# Adafruit_MEMENTO_Camera_LED_Ring.net
KiCad netlist of a schematic drawn in EAGLE
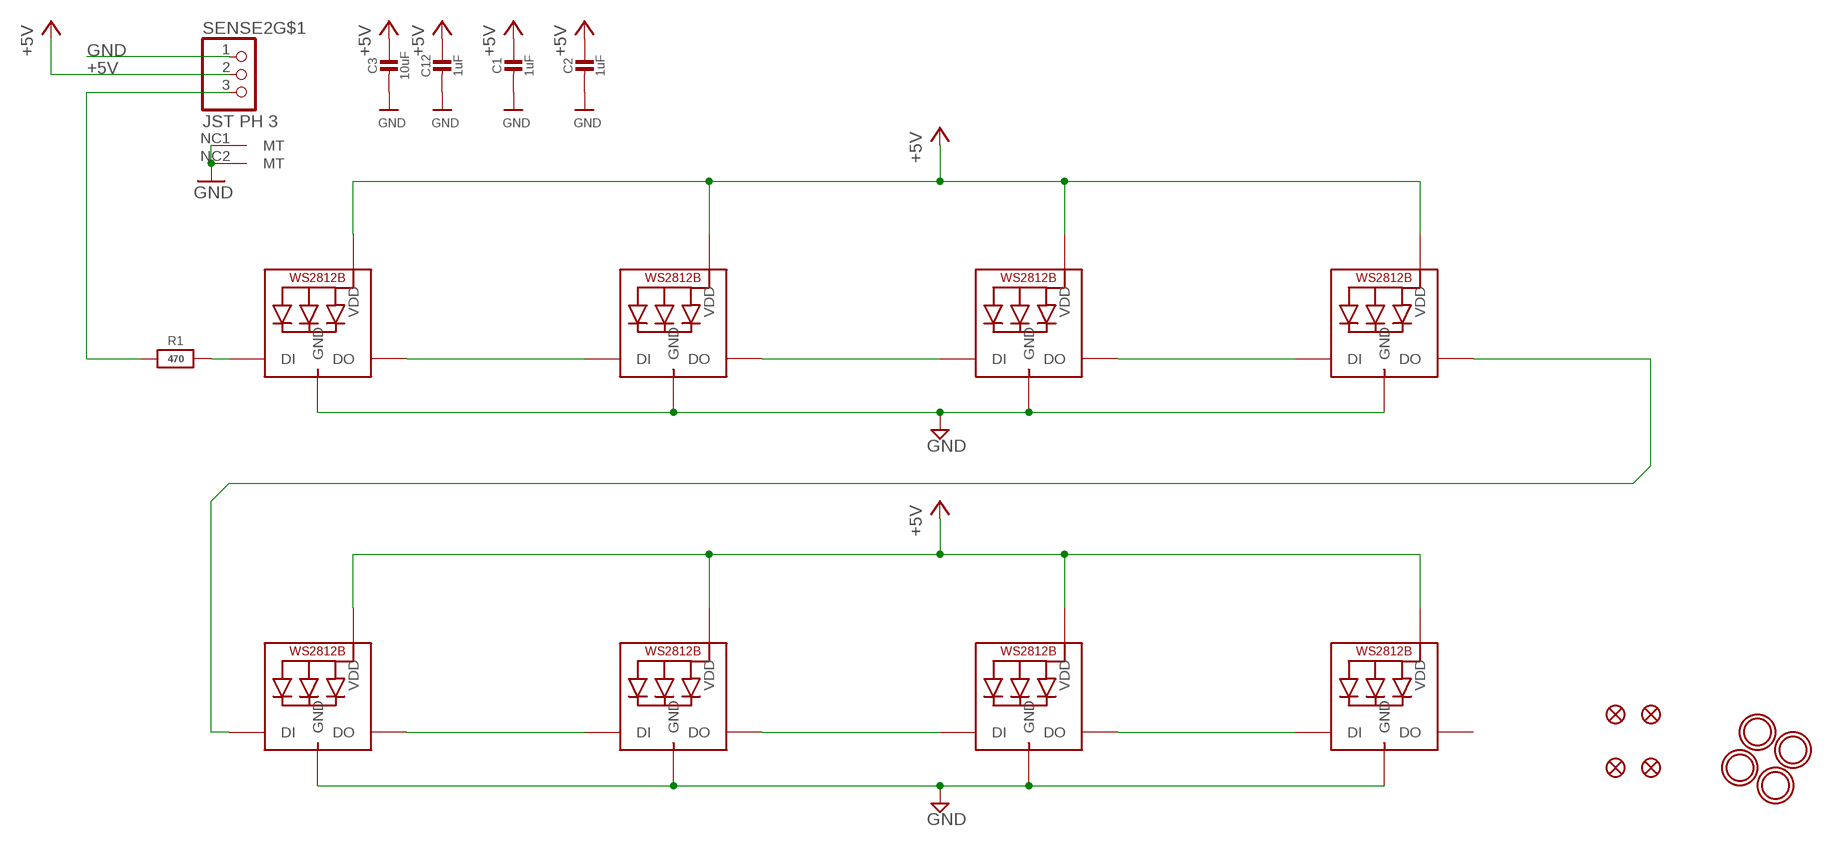
[diagram p0: schematic, sheet 1]

(export (version "E")
  (design (tool "Eeschema 10.0.6"))
  (components
    (comp (ref "C1")
      (value "1uF")
      (footprint "eagle-import:0603-NO")
      (libsource (lib "eagle-import") (part "CAP_CERAMIC0603_NO"))
    )
    (comp (ref "C2")
      (value "1uF")
      (footprint "eagle-import:0603-NO")
      (libsource (lib "eagle-import") (part "CAP_CERAMIC0603_NO"))
    )
    (comp (ref "C3")
      (value "10uF")
      (footprint "eagle-import:0805-NO")
      (libsource (lib "eagle-import") (part "CAP_CERAMIC0805-NOOUTLINE"))
    )
    (comp (ref "C12")
      (value "1uF")
      (footprint "eagle-import:0603-NO")
      (libsource (lib "eagle-import") (part "CAP_CERAMIC0603_NO"))
    )
    (comp (ref "FID1")
      (value "FIDUCIAL_1MM")
      (footprint "eagle-import:FIDUCIAL_1MM")
      (libsource (lib "eagle-import") (part "FIDUCIAL_1MM"))
    )
    (comp (ref "FID2")
      (value "FIDUCIAL_1MM")
      (footprint "eagle-import:FIDUCIAL_1MM")
      (libsource (lib "eagle-import") (part "FIDUCIAL_1MM"))
    )
    (comp (ref "FID3")
      (value "FIDUCIAL_1MM")
      (footprint "eagle-import:FIDUCIAL_1MM")
      (libsource (lib "eagle-import") (part "FIDUCIAL_1MM"))
    )
    (comp (ref "FID4")
      (value "FIDUCIAL_1MM")
      (footprint "eagle-import:FIDUCIAL_1MM")
      (libsource (lib "eagle-import") (part "FIDUCIAL_1MM"))
    )
    (comp (ref "LED1")
      (value "WS2812B_5050N")
      (footprint "eagle-import:WS2812B-NARROW")
      (libsource (lib "eagle-import") (part "WS2812B_5050N"))
    )
    (comp (ref "LED3")
      (value "WS2812B_5050N")
      (footprint "eagle-import:WS2812B-NARROW")
      (libsource (lib "eagle-import") (part "WS2812B_5050N"))
    )
    (comp (ref "LED5")
      (value "WS2812B_5050N")
      (footprint "eagle-import:WS2812B-NARROW")
      (libsource (lib "eagle-import") (part "WS2812B_5050N"))
    )
    (comp (ref "LED7")
      (value "WS2812B_5050N")
      (footprint "eagle-import:WS2812B-NARROW")
      (libsource (lib "eagle-import") (part "WS2812B_5050N"))
    )
    (comp (ref "LED9")
      (value "WS2812B_5050N")
      (footprint "eagle-import:WS2812B-NARROW")
      (libsource (lib "eagle-import") (part "WS2812B_5050N"))
    )
    (comp (ref "LED11")
      (value "WS2812B_5050N")
      (footprint "eagle-import:WS2812B-NARROW")
      (libsource (lib "eagle-import") (part "WS2812B_5050N"))
    )
    (comp (ref "LED13")
      (value "WS2812B_5050N")
      (footprint "eagle-import:WS2812B-NARROW")
      (libsource (lib "eagle-import") (part "WS2812B_5050N"))
    )
    (comp (ref "LED15")
      (value "WS2812B_5050N")
      (footprint "eagle-import:WS2812B-NARROW")
      (libsource (lib "eagle-import") (part "WS2812B_5050N"))
    )
    (comp (ref "R1")
      (value "470")
      (footprint "eagle-import:0603-NO")
      (libsource (lib "eagle-import") (part "RESISTOR_0603_NOOUT"))
    )
    (comp (ref "SENSE2")
      (value "JST PH 3")
      (footprint "eagle-import:JSTPH3")
      (libsource (lib "eagle-import") (part "CON_JST_PH_3PIN"))
    )
    (comp (ref "U$1")
      (value "MOUNTINGHOLE3.0THIN")
      (footprint "eagle-import:MOUNTINGHOLE_3.0_PLATEDTHIN")
      (libsource (lib "eagle-import") (part "MOUNTINGHOLE3.0THIN"))
    )
    (comp (ref "U$2")
      (value "MOUNTINGHOLE3.0THIN")
      (footprint "eagle-import:MOUNTINGHOLE_3.0_PLATEDTHIN")
      (libsource (lib "eagle-import") (part "MOUNTINGHOLE3.0THIN"))
    )
    (comp (ref "U$3")
      (value "MOUNTINGHOLE3.0THIN")
      (footprint "eagle-import:MOUNTINGHOLE_3.0_PLATEDTHIN")
      (libsource (lib "eagle-import") (part "MOUNTINGHOLE3.0THIN"))
    )
    (comp (ref "U$4")
      (value "MOUNTINGHOLE3.0THIN")
      (footprint "eagle-import:MOUNTINGHOLE_3.0_PLATEDTHIN")
      (libsource (lib "eagle-import") (part "MOUNTINGHOLE3.0THIN"))
    )
  )
  (nets
    (net (code "1") (name "+5V") (class "Default")
      (node (ref "C1") (pin "1") (pinfunction "1_1") (pintype "passive"))
      (node (ref "C12") (pin "1") (pinfunction "1_1") (pintype "passive"))
      (node (ref "C2") (pin "1") (pinfunction "1_1") (pintype "passive"))
      (node (ref "C3") (pin "1") (pinfunction "1_1") (pintype "passive"))
      (node (ref "LED1") (pin "1-VDD") (pinfunction "VDD_1-VDD") (pintype "power_in"))
      (node (ref "LED11") (pin "1-VDD") (pinfunction "VDD_1-VDD") (pintype "power_in"))
      (node (ref "LED13") (pin "1-VDD") (pinfunction "VDD_1-VDD") (pintype "power_in"))
      (node (ref "LED15") (pin "1-VDD") (pinfunction "VDD_1-VDD") (pintype "power_in"))
      (node (ref "LED3") (pin "1-VDD") (pinfunction "VDD_1-VDD") (pintype "power_in"))
      (node (ref "LED5") (pin "1-VDD") (pinfunction "VDD_1-VDD") (pintype "power_in"))
      (node (ref "LED7") (pin "1-VDD") (pinfunction "VDD_1-VDD") (pintype "power_in"))
      (node (ref "LED9") (pin "1-VDD") (pinfunction "VDD_1-VDD") (pintype "power_in"))
      (node (ref "SENSE2") (pin "2") (pinfunction "2_2") (pintype "passive"))
    )
    (net (code "2") (name "GND") (class "Default")
      (node (ref "C1") (pin "2") (pinfunction "2_2") (pintype "passive"))
      (node (ref "C12") (pin "2") (pinfunction "2_2") (pintype "passive"))
      (node (ref "C2") (pin "2") (pinfunction "2_2") (pintype "passive"))
      (node (ref "C3") (pin "2") (pinfunction "2_2") (pintype "passive"))
      (node (ref "LED1") (pin "3-GND") (pinfunction "GND_3-GND") (pintype "power_in"))
      (node (ref "LED11") (pin "3-GND") (pinfunction "GND_3-GND") (pintype "power_in"))
      (node (ref "LED13") (pin "3-GND") (pinfunction "GND_3-GND") (pintype "power_in"))
      (node (ref "LED15") (pin "3-GND") (pinfunction "GND_3-GND") (pintype "power_in"))
      (node (ref "LED3") (pin "3-GND") (pinfunction "GND_3-GND") (pintype "power_in"))
      (node (ref "LED5") (pin "3-GND") (pinfunction "GND_3-GND") (pintype "power_in"))
      (node (ref "LED7") (pin "3-GND") (pinfunction "GND_3-GND") (pintype "power_in"))
      (node (ref "LED9") (pin "3-GND") (pinfunction "GND_3-GND") (pintype "power_in"))
      (node (ref "SENSE2") (pin "1") (pinfunction "1_1") (pintype "passive"))
      (node (ref "SENSE2") (pin "NC1") (pinfunction "MT_NC1") (pintype "bidirectional"))
      (node (ref "SENSE2") (pin "NC2") (pinfunction "MT_NC2") (pintype "bidirectional"))
    )
    (net (code "3") (name "Net-(LED1-DI)") (class "Default")
      (node (ref "LED1") (pin "4-DIN") (pinfunction "DI_4-DIN") (pintype "input"))
      (node (ref "R1") (pin "2") (pinfunction "2_2") (pintype "passive"))
    )
    (net (code "4") (name "Net-(LED1-DO)") (class "Default")
      (node (ref "LED1") (pin "2-DOUT") (pinfunction "DO_2-DOUT") (pintype "output"))
      (node (ref "LED3") (pin "4-DIN") (pinfunction "DI_4-DIN") (pintype "input"))
    )
    (net (code "5") (name "Net-(LED3-DO)") (class "Default")
      (node (ref "LED3") (pin "2-DOUT") (pinfunction "DO_2-DOUT") (pintype "output"))
      (node (ref "LED5") (pin "4-DIN") (pinfunction "DI_4-DIN") (pintype "input"))
    )
    (net (code "6") (name "Net-(LED5-DO)") (class "Default")
      (node (ref "LED5") (pin "2-DOUT") (pinfunction "DO_2-DOUT") (pintype "output"))
      (node (ref "LED7") (pin "4-DIN") (pinfunction "DI_4-DIN") (pintype "input"))
    )
    (net (code "7") (name "Net-(LED7-DO)") (class "Default")
      (node (ref "LED7") (pin "2-DOUT") (pinfunction "DO_2-DOUT") (pintype "output"))
      (node (ref "LED9") (pin "4-DIN") (pinfunction "DI_4-DIN") (pintype "input"))
    )
    (net (code "8") (name "Net-(LED11-DI)") (class "Default")
      (node (ref "LED11") (pin "4-DIN") (pinfunction "DI_4-DIN") (pintype "input"))
      (node (ref "LED9") (pin "2-DOUT") (pinfunction "DO_2-DOUT") (pintype "output"))
    )
    (net (code "9") (name "Net-(LED11-DO)") (class "Default")
      (node (ref "LED11") (pin "2-DOUT") (pinfunction "DO_2-DOUT") (pintype "output"))
      (node (ref "LED13") (pin "4-DIN") (pinfunction "DI_4-DIN") (pintype "input"))
    )
    (net (code "10") (name "Net-(LED13-DO)") (class "Default")
      (node (ref "LED13") (pin "2-DOUT") (pinfunction "DO_2-DOUT") (pintype "output"))
      (node (ref "LED15") (pin "4-DIN") (pinfunction "DI_4-DIN") (pintype "input"))
    )
    (net (code "11") (name "Net-(R1-Pad1)") (class "Default")
      (node (ref "R1") (pin "1") (pinfunction "1_1") (pintype "passive"))
      (node (ref "SENSE2") (pin "3") (pinfunction "3_3") (pintype "passive"))
    )
    (net (code "12") (name "unconnected-(LED15-DO-Pad2-DOUT)") (class "Default")
      (node (ref "LED15") (pin "2-DOUT") (pinfunction "DO_2-DOUT") (pintype "output"))
    )
  )
)
